# I-GAUGE_solar_v1-1.net
KiCad netlist of a schematic drawn in EAGLE
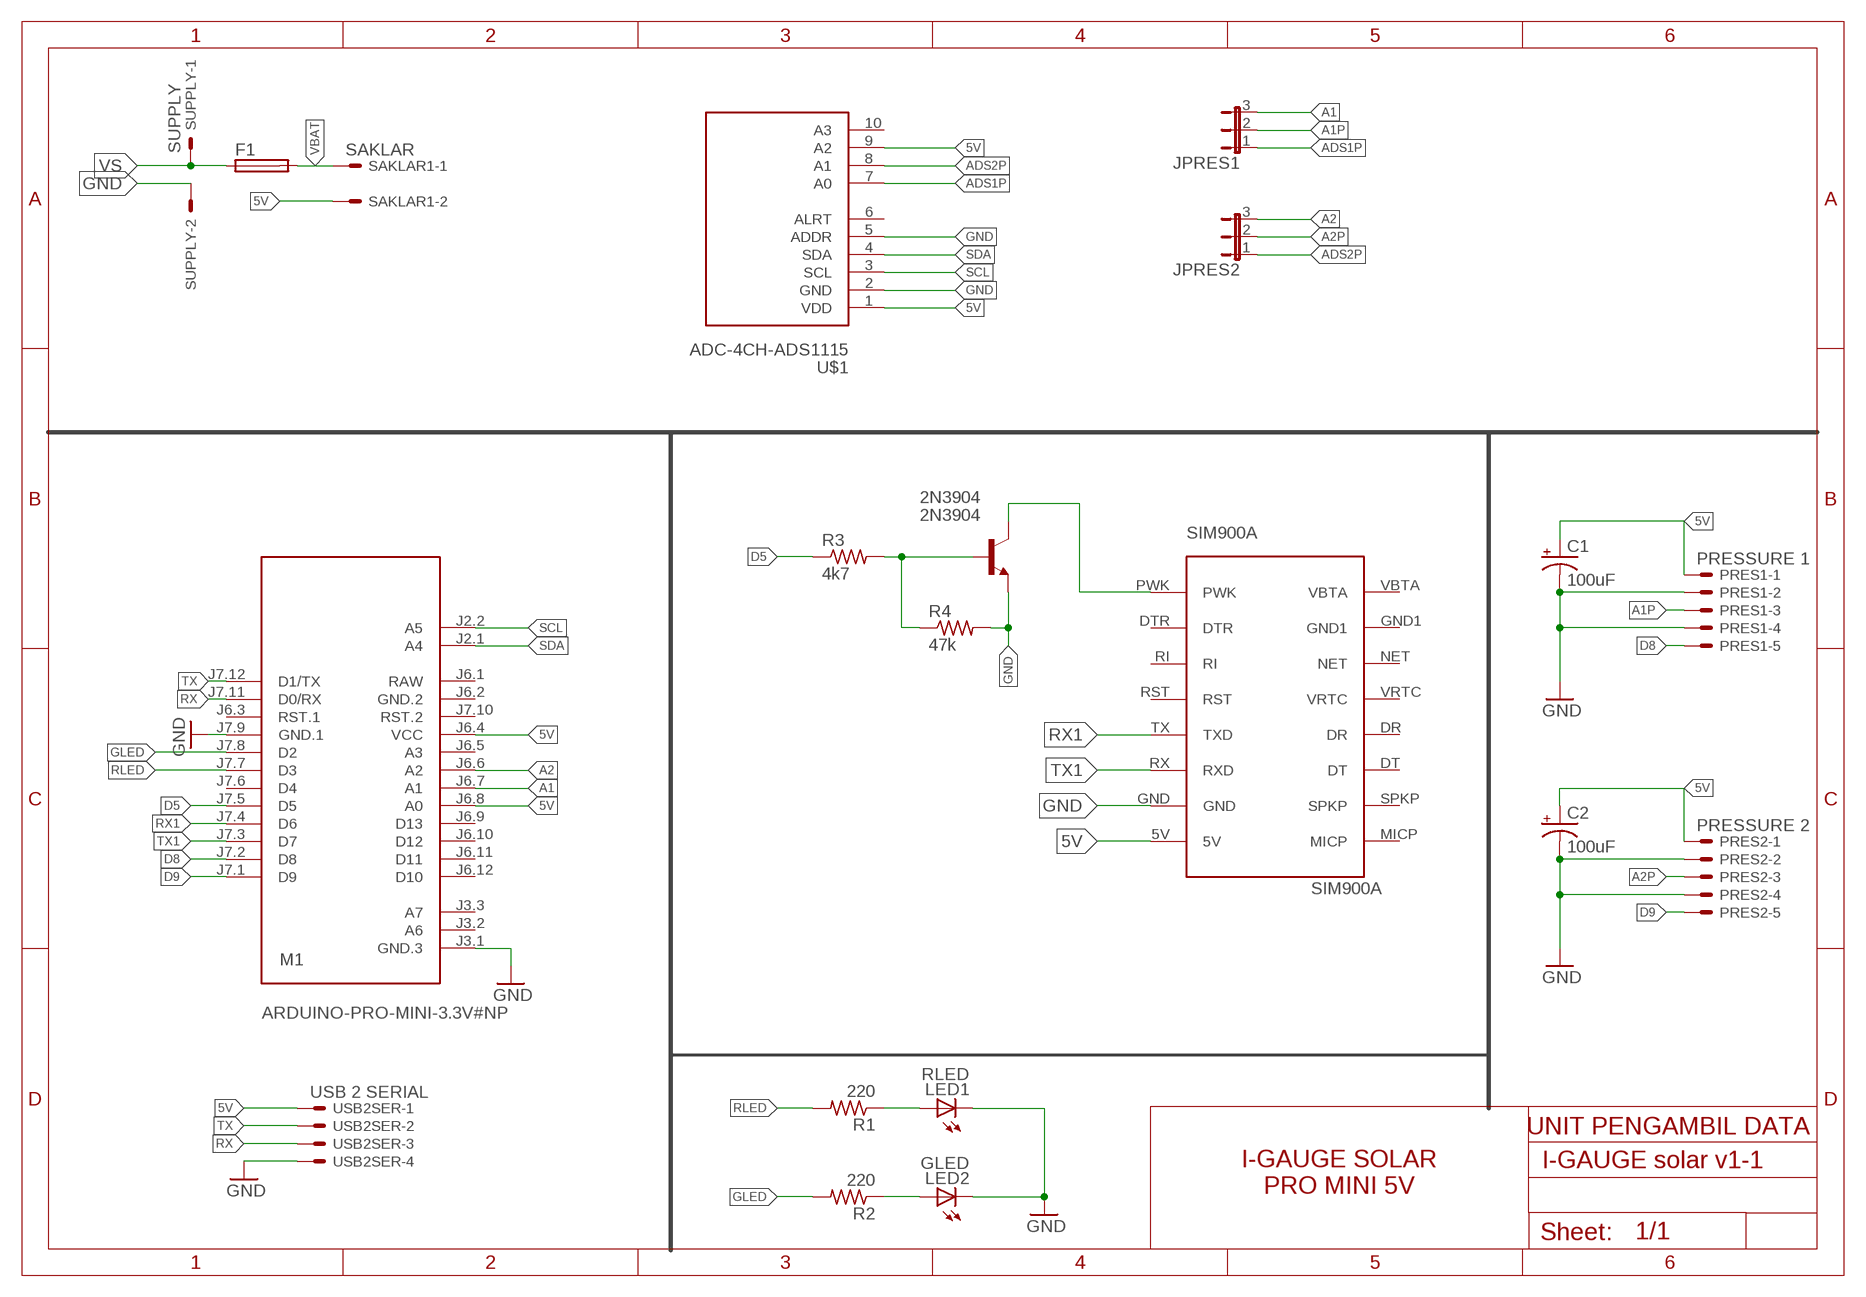
[diagram p0: schematic, sheet 1, part 1 of 2]
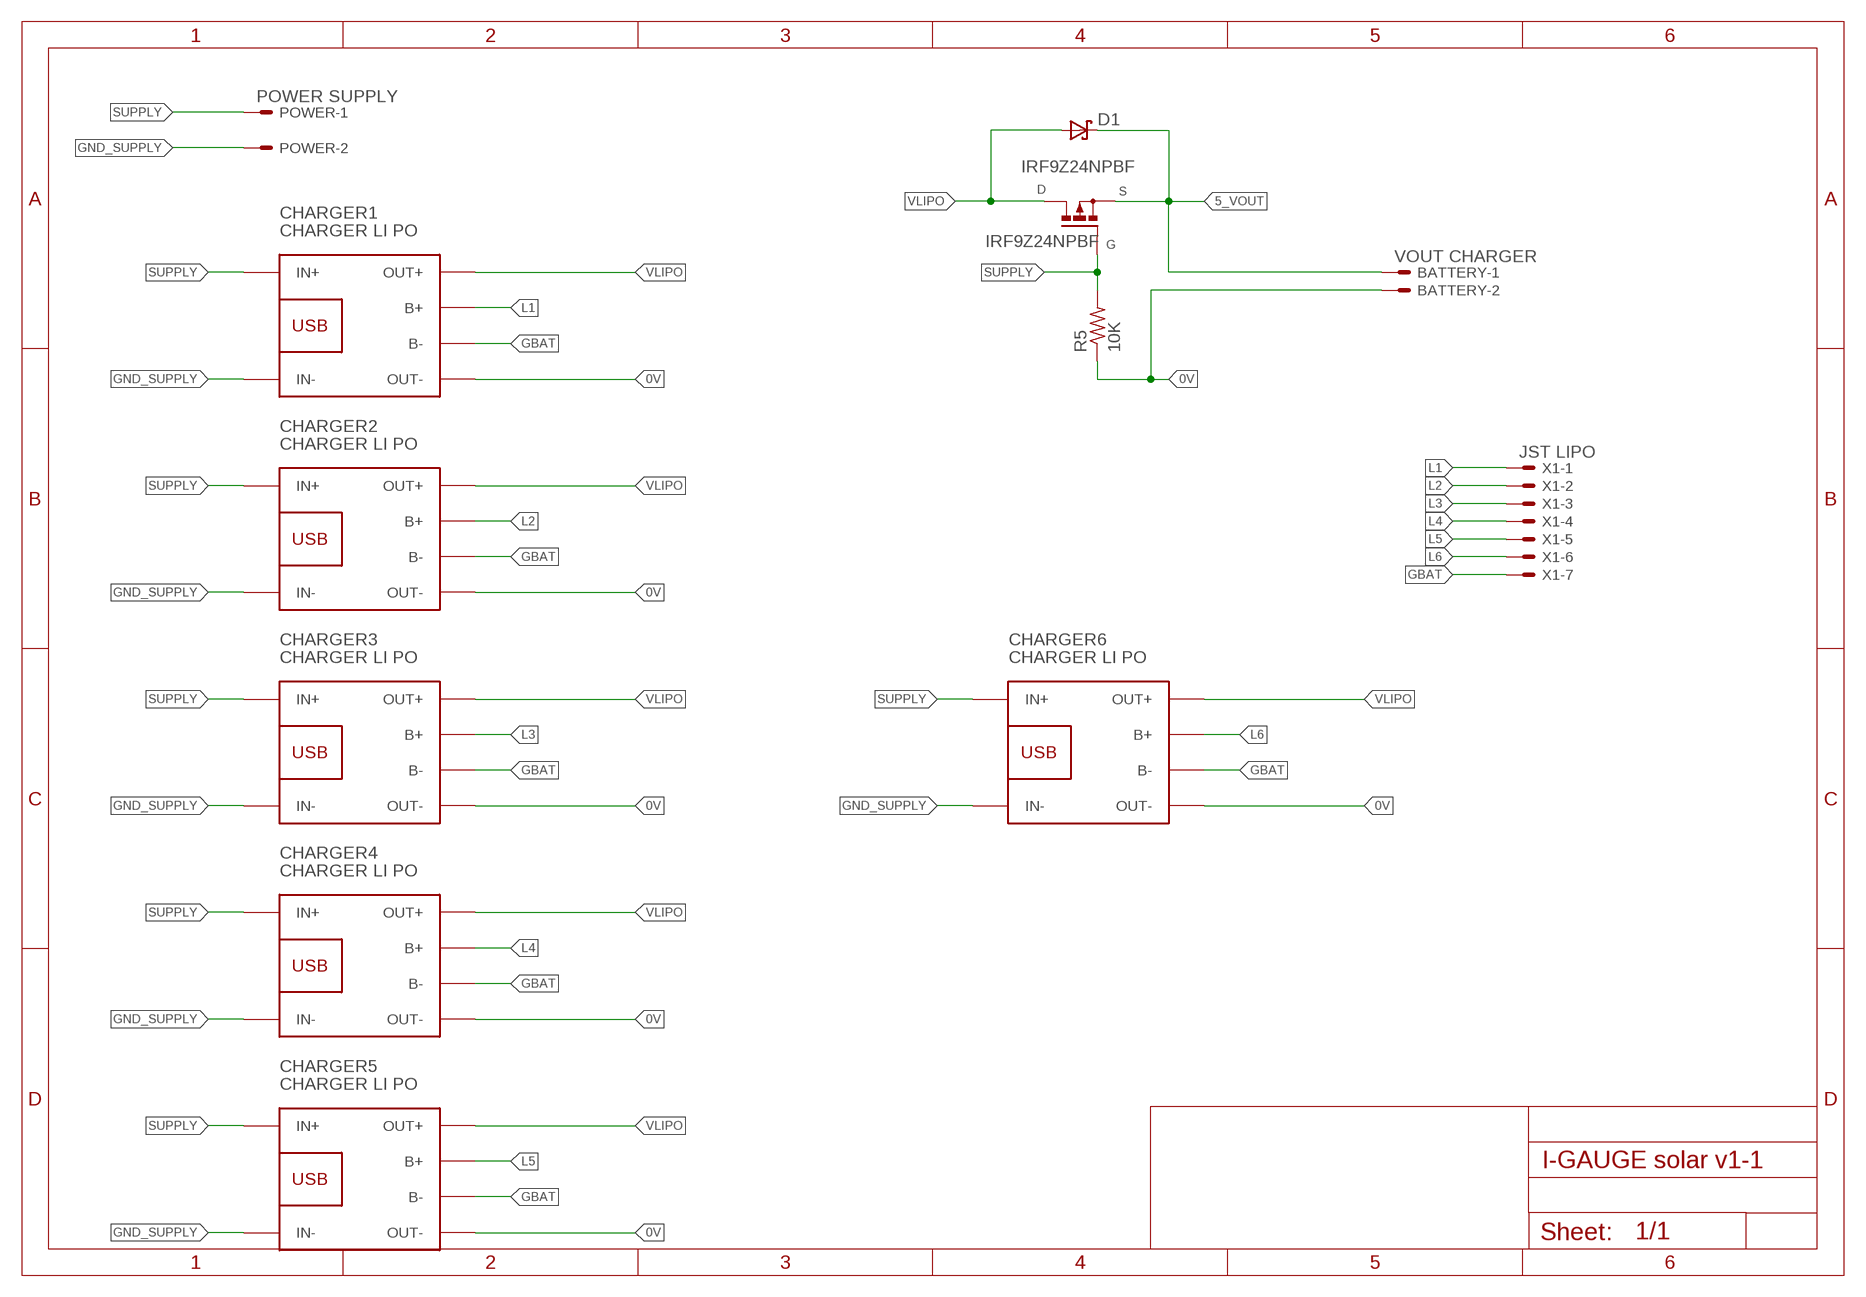
[diagram p1: schematic, sheet 1, part 2 of 2]

(export (version "E")
  (design (tool "Eeschema 10.0.6"))
  (components
    (comp (ref "2N3904")
      (value "2N3904")
      (footprint "eagle-import:TO92")
      (libsource (lib "eagle-import") (part "2N3904"))
    )
    (comp (ref "BATTERY")
      (value "VOUT CHARGER")
      (footprint "eagle-import:JST-XH-02-PACKAGE-ROUND-PAD")
      (libsource (lib "eagle-import") (part "JST-XH-02-PIN-ROUND-PAD"))
    )
    (comp (ref "C1")
      (value "100uF")
      (footprint "eagle-import:EIA7343")
      (libsource (lib "eagle-import") (part "100UF-POLAR-EIA7343-10V-10%(TANT)"))
    )
    (comp (ref "C2")
      (value "100uF")
      (footprint "eagle-import:EIA7343")
      (libsource (lib "eagle-import") (part "100UF-POLAR-EIA7343-10V-10%(TANT)"))
    )
    (comp (ref "CHARGER1")
      (value "CHARGER LI PO")
      (footprint "eagle-import:BATTERY-CHARGER-LI-PROT")
      (libsource (lib "eagle-import") (part "BATTERY-CHARGER-LI-PROT"))
    )
    (comp (ref "CHARGER2")
      (value "CHARGER LI PO")
      (footprint "eagle-import:BATTERY-CHARGER-LI-PROT")
      (libsource (lib "eagle-import") (part "BATTERY-CHARGER-LI-PROT"))
    )
    (comp (ref "CHARGER3")
      (value "CHARGER LI PO")
      (footprint "eagle-import:BATTERY-CHARGER-LI-PROT")
      (libsource (lib "eagle-import") (part "BATTERY-CHARGER-LI-PROT"))
    )
    (comp (ref "CHARGER4")
      (value "CHARGER LI PO")
      (footprint "eagle-import:BATTERY-CHARGER-LI-PROT")
      (libsource (lib "eagle-import") (part "BATTERY-CHARGER-LI-PROT"))
    )
    (comp (ref "CHARGER5")
      (value "CHARGER LI PO")
      (footprint "eagle-import:BATTERY-CHARGER-LI-PROT")
      (libsource (lib "eagle-import") (part "BATTERY-CHARGER-LI-PROT"))
    )
    (comp (ref "CHARGER6")
      (value "CHARGER LI PO")
      (footprint "eagle-import:BATTERY-CHARGER-LI-PROT")
      (libsource (lib "eagle-import") (part "BATTERY-CHARGER-LI-PROT"))
    )
    (comp (ref "D1")
      (value "DS_E2L")
      (footprint "eagle-import:E2LINE")
      (libsource (lib "eagle-import") (part "DS_E2L"))
    )
    (comp (ref "F1")
      (value "FUSESH22,5")
      (footprint "eagle-import:SH22,5")
      (libsource (lib "eagle-import") (part "FUSESH22,5"))
    )
    (comp (ref "IRF9Z24NPBF")
      (value "IRF9Z24NPBF")
      (footprint "eagle-import:TO220BH")
      (libsource (lib "eagle-import") (part "PMOSFET_PTO220BH"))
    )
    (comp (ref "JPRES1")
      (value "JP2E")
      (footprint "eagle-import:JP2")
      (libsource (lib "eagle-import") (part "JP2E"))
    )
    (comp (ref "JPRES2")
      (value "JP2E")
      (footprint "eagle-import:JP2")
      (libsource (lib "eagle-import") (part "JP2E"))
    )
    (comp (ref "LED1")
      (value "RLED")
      (footprint "eagle-import:LED5MM")
      (libsource (lib "eagle-import") (part "LED5MM"))
    )
    (comp (ref "LED2")
      (value "GLED")
      (footprint "eagle-import:LED5MM")
      (libsource (lib "eagle-import") (part "LED5MM"))
    )
    (comp (ref "M1")
      (value "ARDUINO-PRO-MINI-3.3V#NP")
      (footprint "eagle-import:ARDUINO-PRO-MINI#NP")
      (libsource (lib "eagle-import") (part "ARDUINO-PRO-MINI-#NP3.3V"))
    )
    (comp (ref "POWER")
      (value "POWER SUPPLY")
      (footprint "eagle-import:JST-XH-02-PACKAGE-ROUND-PAD")
      (libsource (lib "eagle-import") (part "JST-XH-02-PIN-ROUND-PAD"))
    )
    (comp (ref "PRES1")
      (value "PRESSURE 1")
      (footprint "eagle-import:JST-XH-05-PACKAGE-ROUND-PAD")
      (libsource (lib "eagle-import") (part "JST-XH-05-PIN-ROUND-PAD"))
    )
    (comp (ref "PRES2")
      (value "PRESSURE 2")
      (footprint "eagle-import:JST-XH-05-PACKAGE-ROUND-PAD")
      (libsource (lib "eagle-import") (part "JST-XH-05-PIN-ROUND-PAD"))
    )
    (comp (ref "R1")
      (value "220")
      (footprint "eagle-import:M1206")
      (libsource (lib "eagle-import") (part "resistor_R-US_M1206"))
    )
    (comp (ref "R2")
      (value "220")
      (footprint "eagle-import:M1206")
      (libsource (lib "eagle-import") (part "resistor_R-US_M1206"))
    )
    (comp (ref "R3")
      (value "4k7")
      (footprint "eagle-import:R0805")
      (libsource (lib "eagle-import") (part "R-US_R0805"))
    )
    (comp (ref "R4")
      (value "47k")
      (footprint "eagle-import:R0805")
      (libsource (lib "eagle-import") (part "R-US_R0805"))
    )
    (comp (ref "R5")
      (value "10K")
      (footprint "eagle-import:R0805")
      (libsource (lib "eagle-import") (part "R-US_R0805"))
    )
    (comp (ref "SAKLAR1")
      (value "SAKLAR")
      (footprint "eagle-import:JST-XH-02-PACKAGE-ROUND-PAD")
      (libsource (lib "eagle-import") (part "JST-XH-02-PIN-ROUND-PAD"))
    )
    (comp (ref "SUPPLY")
      (value "SUPPLY")
      (footprint "eagle-import:JST-XH-02-PACKAGE-ROUND-PAD")
      (libsource (lib "eagle-import") (part "JST-XH-02-PIN-ROUND-PAD"))
    )
    (comp (ref "U$1")
      (value "ADC-4CH-ADS1115")
      (footprint "eagle-import:ADC-4CH-ADS1115")
      (libsource (lib "eagle-import") (part "ADC-4CH-ADS1115"))
    )
    (comp (ref "U$5")
      (value "SIM900A")
      (footprint "eagle-import:SIM900A")
      (libsource (lib "eagle-import") (part "SIM900A"))
    )
    (comp (ref "USB2SER")
      (value "USB 2 SERIAL")
      (footprint "eagle-import:JST-XH-04-PACKAGE-ROUND-PAD")
      (libsource (lib "eagle-import") (part "JST-XH-04-PIN-ROUND-PAD"))
    )
    (comp (ref "X1")
      (value "JST LIPO")
      (footprint "eagle-import:JST-XH-07-PACKAGE-ROUND-PAD")
      (libsource (lib "eagle-import") (part "JST-XH-07-PIN-ROUND-PAD"))
    )
  )
  (nets
    (net (code "1") (name "/GND.2") (class "Default")
      (node (ref "M1") (pin "J6.2") (pinfunction "GND.2_J6.2") (pintype "power_in"))
    )
    (net (code "2") (name "/RAW") (class "Default")
      (node (ref "M1") (pin "J6.1") (pinfunction "RAW_J6.1") (pintype "power_in"))
    )
    (net (code "3") (name "0V") (class "Default")
      (node (ref "BATTERY") (pin "2") (pinfunction "S_2") (pintype "passive"))
      (node (ref "CHARGER1") (pin "OUT-") (pinfunction "OUT-_OUT-") (pintype "bidirectional"))
      (node (ref "CHARGER2") (pin "OUT-") (pinfunction "OUT-_OUT-") (pintype "bidirectional"))
      (node (ref "CHARGER3") (pin "OUT-") (pinfunction "OUT-_OUT-") (pintype "bidirectional"))
      (node (ref "CHARGER4") (pin "OUT-") (pinfunction "OUT-_OUT-") (pintype "bidirectional"))
      (node (ref "CHARGER5") (pin "OUT-") (pinfunction "OUT-_OUT-") (pintype "bidirectional"))
      (node (ref "CHARGER6") (pin "OUT-") (pinfunction "OUT-_OUT-") (pintype "bidirectional"))
      (node (ref "R5") (pin "1") (pinfunction "1_1") (pintype "passive"))
    )
    (net (code "4") (name "5V") (class "Default")
      (node (ref "C1") (pin "A") (pinfunction "+_A") (pintype "passive"))
      (node (ref "C2") (pin "A") (pinfunction "+_A") (pintype "passive"))
      (node (ref "M1") (pin "J6.4") (pinfunction "VCC_J6.4") (pintype "power_in"))
      (node (ref "M1") (pin "J6.8") (pinfunction "A0_J6.8") (pintype "bidirectional"))
      (node (ref "PRES1") (pin "1") (pinfunction "S_1") (pintype "passive"))
      (node (ref "PRES2") (pin "1") (pinfunction "S_1") (pintype "passive"))
      (node (ref "SAKLAR1") (pin "2") (pinfunction "S_2") (pintype "passive"))
      (node (ref "U$1") (pin "1") (pinfunction "VDD_1") (pintype "power_in"))
      (node (ref "U$1") (pin "9") (pinfunction "A2_9") (pintype "input"))
      (node (ref "U$5") (pin "5V") (pinfunction "5V_5V") (pintype "bidirectional"))
      (node (ref "USB2SER") (pin "1") (pinfunction "S_1") (pintype "passive"))
    )
    (net (code "5") (name "5_VOUT") (class "Default")
      (node (ref "BATTERY") (pin "1") (pinfunction "S_1") (pintype "passive"))
      (node (ref "D1") (pin "1") (pinfunction "K_1") (pintype "passive"))
      (node (ref "IRF9Z24NPBF") (pin "S") (pinfunction "S_S") (pintype "passive"))
    )
    (net (code "6") (name "A1") (class "Default")
      (node (ref "JPRES1") (pin "3") (pinfunction "3_3") (pintype "passive"))
      (node (ref "M1") (pin "J6.7") (pinfunction "A1_J6.7") (pintype "bidirectional"))
    )
    (net (code "7") (name "A1P") (class "Default")
      (node (ref "JPRES1") (pin "2") (pinfunction "2_2") (pintype "passive"))
      (node (ref "PRES1") (pin "3") (pinfunction "S_3") (pintype "passive"))
    )
    (net (code "8") (name "A2") (class "Default")
      (node (ref "JPRES2") (pin "3") (pinfunction "3_3") (pintype "passive"))
      (node (ref "M1") (pin "J6.6") (pinfunction "A2_J6.6") (pintype "bidirectional"))
    )
    (net (code "9") (name "A2P") (class "Default")
      (node (ref "JPRES2") (pin "2") (pinfunction "2_2") (pintype "passive"))
      (node (ref "PRES2") (pin "3") (pinfunction "S_3") (pintype "passive"))
    )
    (net (code "10") (name "ADS1P") (class "Default")
      (node (ref "JPRES1") (pin "1") (pinfunction "1_1") (pintype "passive"))
      (node (ref "U$1") (pin "7") (pinfunction "A0_7") (pintype "input"))
    )
    (net (code "11") (name "ADS2P") (class "Default")
      (node (ref "JPRES2") (pin "1") (pinfunction "1_1") (pintype "passive"))
      (node (ref "U$1") (pin "8") (pinfunction "A1_8") (pintype "input"))
    )
    (net (code "12") (name "D5") (class "Default")
      (node (ref "M1") (pin "J7.5") (pinfunction "D5_J7.5") (pintype "bidirectional"))
      (node (ref "R3") (pin "1") (pinfunction "1_1") (pintype "passive"))
    )
    (net (code "13") (name "D8") (class "Default")
      (node (ref "M1") (pin "J7.2") (pinfunction "D8_J7.2") (pintype "bidirectional"))
      (node (ref "PRES1") (pin "5") (pinfunction "S_5") (pintype "passive"))
    )
    (net (code "14") (name "D9") (class "Default")
      (node (ref "M1") (pin "J7.1") (pinfunction "D9_J7.1") (pintype "bidirectional"))
      (node (ref "PRES2") (pin "5") (pinfunction "S_5") (pintype "passive"))
    )
    (net (code "15") (name "GBAT") (class "Default")
      (node (ref "CHARGER1") (pin "B-") (pinfunction "B-_B-") (pintype "bidirectional"))
      (node (ref "CHARGER2") (pin "B-") (pinfunction "B-_B-") (pintype "bidirectional"))
      (node (ref "CHARGER3") (pin "B-") (pinfunction "B-_B-") (pintype "bidirectional"))
      (node (ref "CHARGER4") (pin "B-") (pinfunction "B-_B-") (pintype "bidirectional"))
      (node (ref "CHARGER5") (pin "B-") (pinfunction "B-_B-") (pintype "bidirectional"))
      (node (ref "CHARGER6") (pin "B-") (pinfunction "B-_B-") (pintype "bidirectional"))
      (node (ref "X1") (pin "7") (pinfunction "S_7") (pintype "passive"))
    )
    (net (code "16") (name "GLED") (class "Default")
      (node (ref "M1") (pin "J7.8") (pinfunction "D2_J7.8") (pintype "bidirectional"))
      (node (ref "R2") (pin "2") (pinfunction "2_2") (pintype "passive"))
    )
    (net (code "17") (name "GND") (class "Default")
      (node (ref "2N3904") (pin "3") (pinfunction "E_3") (pintype "passive"))
      (node (ref "C1") (pin "C") (pinfunction "-_C") (pintype "passive"))
      (node (ref "C2") (pin "C") (pinfunction "-_C") (pintype "passive"))
      (node (ref "LED1") (pin "K") (pinfunction "C_K") (pintype "passive"))
      (node (ref "LED2") (pin "K") (pinfunction "C_K") (pintype "passive"))
      (node (ref "M1") (pin "J3.1") (pinfunction "GND.3_J3.1") (pintype "bidirectional"))
      (node (ref "M1") (pin "J7.9") (pinfunction "GND.1_J7.9") (pintype "power_in"))
      (node (ref "PRES1") (pin "2") (pinfunction "S_2") (pintype "passive"))
      (node (ref "PRES1") (pin "4") (pinfunction "S_4") (pintype "passive"))
      (node (ref "PRES2") (pin "2") (pinfunction "S_2") (pintype "passive"))
      (node (ref "PRES2") (pin "4") (pinfunction "S_4") (pintype "passive"))
      (node (ref "R4") (pin "2") (pinfunction "2_2") (pintype "passive"))
      (node (ref "SUPPLY") (pin "2") (pinfunction "S_2") (pintype "passive"))
      (node (ref "U$1") (pin "2") (pinfunction "GND_2") (pintype "power_in"))
      (node (ref "U$1") (pin "5") (pinfunction "ADDR_5") (pintype "bidirectional"))
      (node (ref "U$5") (pin "GND") (pinfunction "GND_GND") (pintype "bidirectional"))
      (node (ref "USB2SER") (pin "4") (pinfunction "S_4") (pintype "passive"))
    )
    (net (code "18") (name "GND_SUPPLY") (class "Default")
      (node (ref "CHARGER1") (pin "IN-") (pinfunction "IN-_IN-") (pintype "bidirectional"))
      (node (ref "CHARGER2") (pin "IN-") (pinfunction "IN-_IN-") (pintype "bidirectional"))
      (node (ref "CHARGER3") (pin "IN-") (pinfunction "IN-_IN-") (pintype "bidirectional"))
      (node (ref "CHARGER4") (pin "IN-") (pinfunction "IN-_IN-") (pintype "bidirectional"))
      (node (ref "CHARGER5") (pin "IN-") (pinfunction "IN-_IN-") (pintype "bidirectional"))
      (node (ref "CHARGER6") (pin "IN-") (pinfunction "IN-_IN-") (pintype "bidirectional"))
      (node (ref "POWER") (pin "2") (pinfunction "S_2") (pintype "passive"))
    )
    (net (code "19") (name "L1") (class "Default")
      (node (ref "CHARGER1") (pin "B+") (pinfunction "B+_B+") (pintype "bidirectional"))
      (node (ref "X1") (pin "1") (pinfunction "S_1") (pintype "passive"))
    )
    (net (code "20") (name "L2") (class "Default")
      (node (ref "CHARGER2") (pin "B+") (pinfunction "B+_B+") (pintype "bidirectional"))
      (node (ref "X1") (pin "2") (pinfunction "S_2") (pintype "passive"))
    )
    (net (code "21") (name "L3") (class "Default")
      (node (ref "CHARGER3") (pin "B+") (pinfunction "B+_B+") (pintype "bidirectional"))
      (node (ref "X1") (pin "3") (pinfunction "S_3") (pintype "passive"))
    )
    (net (code "22") (name "L4") (class "Default")
      (node (ref "CHARGER4") (pin "B+") (pinfunction "B+_B+") (pintype "bidirectional"))
      (node (ref "X1") (pin "4") (pinfunction "S_4") (pintype "passive"))
    )
    (net (code "23") (name "L5") (class "Default")
      (node (ref "CHARGER5") (pin "B+") (pinfunction "B+_B+") (pintype "bidirectional"))
      (node (ref "X1") (pin "5") (pinfunction "S_5") (pintype "passive"))
    )
    (net (code "24") (name "L6") (class "Default")
      (node (ref "CHARGER6") (pin "B+") (pinfunction "B+_B+") (pintype "bidirectional"))
      (node (ref "X1") (pin "6") (pinfunction "S_6") (pintype "passive"))
    )
    (net (code "25") (name "Net-(2N3904-B)") (class "Default")
      (node (ref "2N3904") (pin "2") (pinfunction "B_2") (pintype "passive"))
      (node (ref "R3") (pin "2") (pinfunction "2_2") (pintype "passive"))
      (node (ref "R4") (pin "1") (pinfunction "1_1") (pintype "passive"))
    )
    (net (code "26") (name "Net-(2N3904-C)") (class "Default")
      (node (ref "2N3904") (pin "1") (pinfunction "C_1") (pintype "passive"))
      (node (ref "U$5") (pin "PWK") (pinfunction "PWK_PWK") (pintype "bidirectional"))
    )
    (net (code "27") (name "Net-(LED1-PadA)") (class "Default")
      (node (ref "LED1") (pin "A") (pinfunction "A_A") (pintype "passive"))
      (node (ref "R1") (pin "1") (pinfunction "1_1") (pintype "passive"))
    )
    (net (code "28") (name "Net-(LED2-PadA)") (class "Default")
      (node (ref "LED2") (pin "A") (pinfunction "A_A") (pintype "passive"))
      (node (ref "R2") (pin "1") (pinfunction "1_1") (pintype "passive"))
    )
    (net (code "29") (name "RLED") (class "Default")
      (node (ref "M1") (pin "J7.7") (pinfunction "D3_J7.7") (pintype "bidirectional"))
      (node (ref "R1") (pin "2") (pinfunction "2_2") (pintype "passive"))
    )
    (net (code "30") (name "RX") (class "Default")
      (node (ref "M1") (pin "J7.11") (pinfunction "D0/RX_J7.11") (pintype "bidirectional"))
      (node (ref "USB2SER") (pin "3") (pinfunction "S_3") (pintype "passive"))
    )
    (net (code "31") (name "RX1") (class "Default")
      (node (ref "M1") (pin "J7.4") (pinfunction "D6_J7.4") (pintype "bidirectional"))
      (node (ref "U$5") (pin "TX") (pinfunction "TXD_TX") (pintype "bidirectional"))
    )
    (net (code "32") (name "SCL") (class "Default")
      (node (ref "M1") (pin "J2.2") (pinfunction "A5_J2.2") (pintype "bidirectional"))
      (node (ref "U$1") (pin "3") (pinfunction "SCL_3") (pintype "bidirectional"))
    )
    (net (code "33") (name "SDA") (class "Default")
      (node (ref "M1") (pin "J2.1") (pinfunction "A4_J2.1") (pintype "bidirectional"))
      (node (ref "U$1") (pin "4") (pinfunction "SDA_4") (pintype "bidirectional"))
    )
    (net (code "34") (name "SUPPLY") (class "Default")
      (node (ref "CHARGER1") (pin "IN+") (pinfunction "IN+_IN+") (pintype "bidirectional"))
      (node (ref "CHARGER2") (pin "IN+") (pinfunction "IN+_IN+") (pintype "bidirectional"))
      (node (ref "CHARGER3") (pin "IN+") (pinfunction "IN+_IN+") (pintype "bidirectional"))
      (node (ref "CHARGER4") (pin "IN+") (pinfunction "IN+_IN+") (pintype "bidirectional"))
      (node (ref "CHARGER5") (pin "IN+") (pinfunction "IN+_IN+") (pintype "bidirectional"))
      (node (ref "CHARGER6") (pin "IN+") (pinfunction "IN+_IN+") (pintype "bidirectional"))
      (node (ref "IRF9Z24NPBF") (pin "G") (pinfunction "G_G") (pintype "passive"))
      (node (ref "POWER") (pin "1") (pinfunction "S_1") (pintype "passive"))
      (node (ref "R5") (pin "2") (pinfunction "2_2") (pintype "passive"))
    )
    (net (code "35") (name "TX") (class "Default")
      (node (ref "M1") (pin "J7.12") (pinfunction "D1/TX_J7.12") (pintype "bidirectional"))
      (node (ref "USB2SER") (pin "2") (pinfunction "S_2") (pintype "passive"))
    )
    (net (code "36") (name "TX1") (class "Default")
      (node (ref "M1") (pin "J7.3") (pinfunction "D7_J7.3") (pintype "bidirectional"))
      (node (ref "U$5") (pin "RX") (pinfunction "RXD_RX") (pintype "bidirectional"))
    )
    (net (code "37") (name "VBAT") (class "Default")
      (node (ref "F1") (pin "2") (pinfunction "2_2") (pintype "passive"))
      (node (ref "SAKLAR1") (pin "1") (pinfunction "S_1") (pintype "passive"))
    )
    (net (code "38") (name "VLIPO") (class "Default")
      (node (ref "CHARGER1") (pin "OUT+") (pinfunction "OUT+_OUT+") (pintype "bidirectional"))
      (node (ref "CHARGER2") (pin "OUT+") (pinfunction "OUT+_OUT+") (pintype "bidirectional"))
      (node (ref "CHARGER3") (pin "OUT+") (pinfunction "OUT+_OUT+") (pintype "bidirectional"))
      (node (ref "CHARGER4") (pin "OUT+") (pinfunction "OUT+_OUT+") (pintype "bidirectional"))
      (node (ref "CHARGER5") (pin "OUT+") (pinfunction "OUT+_OUT+") (pintype "bidirectional"))
      (node (ref "CHARGER6") (pin "OUT+") (pinfunction "OUT+_OUT+") (pintype "bidirectional"))
      (node (ref "D1") (pin "2") (pinfunction "A_2") (pintype "passive"))
      (node (ref "IRF9Z24NPBF") (pin "D") (pinfunction "D_D") (pintype "passive"))
    )
    (net (code "39") (name "VS") (class "Default")
      (node (ref "F1") (pin "1") (pinfunction "1_1") (pintype "passive"))
      (node (ref "SUPPLY") (pin "1") (pinfunction "S_1") (pintype "passive"))
    )
    (net (code "40") (name "unconnected-(M1-A3-PadJ6.5)") (class "Default")
      (node (ref "M1") (pin "J6.5") (pinfunction "A3_J6.5") (pintype "bidirectional"))
    )
    (net (code "41") (name "unconnected-(M1-A6-PadJ3.2)") (class "Default")
      (node (ref "M1") (pin "J3.2") (pinfunction "A6_J3.2") (pintype "bidirectional"))
    )
    (net (code "42") (name "unconnected-(M1-A7-PadJ3.3)") (class "Default")
      (node (ref "M1") (pin "J3.3") (pinfunction "A7_J3.3") (pintype "bidirectional"))
    )
    (net (code "43") (name "unconnected-(M1-D4-PadJ7.6)") (class "Default")
      (node (ref "M1") (pin "J7.6") (pinfunction "D4_J7.6") (pintype "bidirectional"))
    )
    (net (code "44") (name "unconnected-(M1-D10-PadJ6.12)") (class "Default")
      (node (ref "M1") (pin "J6.12") (pinfunction "D10_J6.12") (pintype "bidirectional"))
    )
    (net (code "45") (name "unconnected-(M1-D11-PadJ6.11)") (class "Default")
      (node (ref "M1") (pin "J6.11") (pinfunction "D11_J6.11") (pintype "bidirectional"))
    )
    (net (code "46") (name "unconnected-(M1-D12-PadJ6.10)") (class "Default")
      (node (ref "M1") (pin "J6.10") (pinfunction "D12_J6.10") (pintype "bidirectional"))
    )
    (net (code "47") (name "unconnected-(M1-D13-PadJ6.9)") (class "Default")
      (node (ref "M1") (pin "J6.9") (pinfunction "D13_J6.9") (pintype "bidirectional"))
    )
    (net (code "48") (name "unconnected-(M1-RST.1-PadJ6.3)") (class "Default")
      (node (ref "M1") (pin "J6.3") (pinfunction "RST.1_J6.3") (pintype "bidirectional"))
    )
    (net (code "49") (name "unconnected-(M1-RST.2-PadJ7.10)") (class "Default")
      (node (ref "M1") (pin "J7.10") (pinfunction "RST.2_J7.10") (pintype "bidirectional"))
    )
    (net (code "50") (name "unconnected-(U$1-A3-Pad10)") (class "Default")
      (node (ref "U$1") (pin "10") (pinfunction "A3_10") (pintype "input"))
    )
    (net (code "51") (name "unconnected-(U$1-ALRT-Pad6)") (class "Default")
      (node (ref "U$1") (pin "6") (pinfunction "ALRT_6") (pintype "bidirectional"))
    )
    (net (code "52") (name "unconnected-(U$5-PadDR)") (class "Default")
      (node (ref "U$5") (pin "DR") (pinfunction "DR_DR") (pintype "bidirectional"))
    )
    (net (code "53") (name "unconnected-(U$5-PadDT)") (class "Default")
      (node (ref "U$5") (pin "DT") (pinfunction "DT_DT") (pintype "bidirectional"))
    )
    (net (code "54") (name "unconnected-(U$5-PadDTR)") (class "Default")
      (node (ref "U$5") (pin "DTR") (pinfunction "DTR_DTR") (pintype "bidirectional"))
    )
    (net (code "55") (name "unconnected-(U$5-PadGND1)") (class "Default")
      (node (ref "U$5") (pin "GND1") (pinfunction "GND1_GND1") (pintype "bidirectional"))
    )
    (net (code "56") (name "unconnected-(U$5-PadMICP)") (class "Default")
      (node (ref "U$5") (pin "MICP") (pinfunction "MICP_MICP") (pintype "bidirectional"))
    )
    (net (code "57") (name "unconnected-(U$5-PadNET)") (class "Default")
      (node (ref "U$5") (pin "NET") (pinfunction "NET_NET") (pintype "bidirectional"))
    )
    (net (code "58") (name "unconnected-(U$5-PadRI)") (class "Default")
      (node (ref "U$5") (pin "RI") (pinfunction "RI_RI") (pintype "bidirectional"))
    )
    (net (code "59") (name "unconnected-(U$5-PadRST)") (class "Default")
      (node (ref "U$5") (pin "RST") (pinfunction "RST_RST") (pintype "bidirectional"))
    )
    (net (code "60") (name "unconnected-(U$5-PadSPKP)") (class "Default")
      (node (ref "U$5") (pin "SPKP") (pinfunction "SPKP_SPKP") (pintype "bidirectional"))
    )
    (net (code "61") (name "unconnected-(U$5-PadVBTA)") (class "Default")
      (node (ref "U$5") (pin "VBTA") (pinfunction "VBTA_VBTA") (pintype "bidirectional"))
    )
    (net (code "62") (name "unconnected-(U$5-PadVRTC)") (class "Default")
      (node (ref "U$5") (pin "VRTC") (pinfunction "VRTC_VRTC") (pintype "bidirectional"))
    )
  )
)
